# GPS_Module.net
KiCad netlist of a schematic drawn in Altium Designer
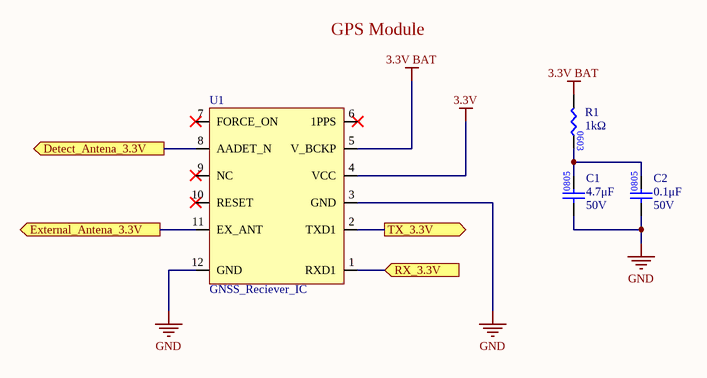
[diagram p0: GPS_Module.SchDoc]

(export (version "E")
  (design (tool "Eeschema 10.0.6"))
  (components
    (comp (ref "C1")
      (value "4.7μF")
      (footprint "CAP0805")
      (description "CAP CER 4.7UF 50V X5R 0805")
      (fields
        (field (name "LCSC PART #") "C1779")
        (field (name "VOLTAGE RATING") "50V")
        (field (name "Comment") "CAP_4.7uF_50V_0805")
      )
      (libsource (lib "UWRT_Schematic_Library_2020") (part "CAP_4.7uF_50V_0805"))
    )
    (comp (ref "C2")
      (value "0.1μF")
      (footprint "CAP0805")
      (description "CAP CER 0.1UF 50V X7R 0805")
      (fields
        (field (name "LCSC PART #") "C49678")
        (field (name "VOLTAGE RATING") "50V")
        (field (name "Comment") "CAP_0.1uF_50V_0805")
      )
      (libsource (lib "UWRT_Schematic_Library_2020") (part "CAP_0.1uF_50V_0805"))
    )
    (comp (ref "R1")
      (value "1kΩ")
      (footprint "RES0603")
      (description "RES 1K OHM 5% 1/10W 0603")
      (fields (field (name "Comment") "RES_1kΩ_0603_5%"))
      (libsource (lib "UWRT_Schematic_Library_2020") (part "RES_1kΩ_0603_5%"))
    )
    (comp (ref "U1")
      (value "GNSS_Reciever_IC")
      (footprint "L86_M33_GNSS_Reciever_IC")
      (fields (field (name "MANUFACTURER") "Quectel"))
      (libsource (lib "UWRT_Schematic_Library_2020") (part "GNSS_Reciever_IC"))
    )
  )
  (nets
    (net (code "1") (name "/Detect_Antena_3.3V") (class "Default")
      (node (ref "U1") (pin "8") (pinfunction "AADET_N_8") (pintype "passive"))
    )
    (net (code "2") (name "/External_Antena_3.3V") (class "Default")
      (node (ref "U1") (pin "11") (pinfunction "EX_ANT_11") (pintype "passive"))
    )
    (net (code "3") (name "/RX_3.3V") (class "Default")
      (node (ref "U1") (pin "1") (pinfunction "RXD1_1") (pintype "passive"))
    )
    (net (code "4") (name "/TX_3.3V") (class "Default")
      (node (ref "U1") (pin "2") (pinfunction "TXD1_2") (pintype "passive"))
    )
    (net (code "5") (name "3.3V") (class "Default")
      (node (ref "U1") (pin "4") (pinfunction "VCC_4") (pintype "passive"))
    )
    (net (code "6") (name "3.3V BAT") (class "Default")
      (node (ref "R1") (pin "1") (pinfunction "1_1") (pintype "passive"))
      (node (ref "U1") (pin "5") (pinfunction "V_BCKP_5") (pintype "passive"))
    )
    (net (code "7") (name "GND") (class "Default")
      (node (ref "C1") (pin "1") (pinfunction "1_1") (pintype "passive"))
      (node (ref "C2") (pin "1") (pinfunction "1_1") (pintype "passive"))
      (node (ref "U1") (pin "12") (pinfunction "GND_12") (pintype "passive"))
      (node (ref "U1") (pin "3") (pinfunction "GND_3") (pintype "passive"))
    )
    (net (code "8") (name "Net-(C1-Pad2)") (class "Default")
      (node (ref "C1") (pin "2") (pinfunction "2_2") (pintype "passive"))
      (node (ref "C2") (pin "2") (pinfunction "2_2") (pintype "passive"))
      (node (ref "R1") (pin "2") (pinfunction "2_2") (pintype "passive"))
    )
    (net (code "9") (name "unconnected-(U1-1PPS-Pad6)") (class "Default")
      (node (ref "U1") (pin "6") (pinfunction "1PPS_6") (pintype "passive+no_connect"))
    )
    (net (code "10") (name "unconnected-(U1-FORCE_ON-Pad7)") (class "Default")
      (node (ref "U1") (pin "7") (pinfunction "FORCE_ON_7") (pintype "passive+no_connect"))
    )
    (net (code "11") (name "unconnected-(U1-NC-Pad9)") (class "Default")
      (node (ref "U1") (pin "9") (pinfunction "NC_9") (pintype "passive+no_connect"))
    )
    (net (code "12") (name "unconnected-(U1-RESET-Pad10)") (class "Default")
      (node (ref "U1") (pin "10") (pinfunction "RESET_10") (pintype "passive+no_connect"))
    )
  )
)
